# CH340T-BREAKOUT.net
KiCad netlist of a schematic drawn in Altium Designer
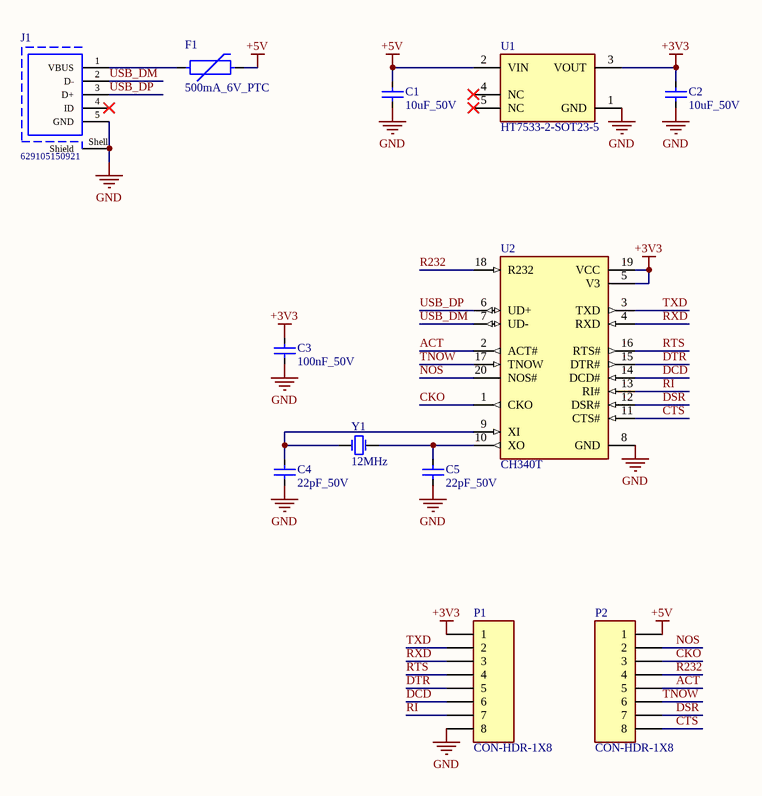
[diagram p0: CH340T-BREAKOUT.SchDoc]

(export (version "E")
  (design (tool "Eeschema 10.0.6"))
  (components
    (comp (ref "C1")
      (value "10uF_50V")
      (footprint "CustomLib-Package:C0805")
      (description "C0805 0.10 μF X7R 30ppm/°C 10.00% 50 V")
      (fields
        (field (name "MANUFACTURER") "KEMET")
        (field (name "MANUFACTURER PART NUMBER") "C0805C104K5RAC7411")
      )
      (libsource (lib "CustomLib-Package") (part "CAPACITOR"))
    )
    (comp (ref "C2")
      (value "10uF_50V")
      (footprint "CustomLib-Package:C0805")
      (description "C0805 0.10 μF X7R 30ppm/°C 10.00% 50 V")
      (fields
        (field (name "MANUFACTURER") "KEMET")
        (field (name "MANUFACTURER PART NUMBER") "C0805C104K5RAC7411")
      )
      (libsource (lib "CustomLib-Package") (part "CAPACITOR"))
    )
    (comp (ref "C3")
      (value "100nF_50V")
      (footprint "CustomLib-Package:C0805")
      (description "C0805 0.10 μF X7R 30ppm/°C 10.00% 50 V")
      (fields
        (field (name "MANUFACTURER") "KEMET")
        (field (name "MANUFACTURER PART NUMBER") "C0805C104K5RAC7411")
      )
      (libsource (lib "CustomLib-Package") (part "CAPACITOR"))
    )
    (comp (ref "C4")
      (value "22pF_50V")
      (footprint "CustomLib-Package:C0805")
      (description "Cap Ceramic 22pF 50V C0G 5% SMD 0603")
      (fields (field (name "Comment") "C0603C220J5GACAUTO"))
      (libsource (lib "CustomLib-Package") (part "CAPACITOR"))
    )
    (comp (ref "C5")
      (value "22pF_50V")
      (footprint "CustomLib-Package:C0805")
      (description "Cap Ceramic 22pF 50V C0G 5% SMD 0603")
      (fields (field (name "Comment") "C0603C220J5GACAUTO"))
      (libsource (lib "CustomLib-Package") (part "CAPACITOR"))
    )
    (comp (ref "F1")
      (value "500mA_6V_PTC")
      (footprint "R0805")
      (description "FUSE 500MA SMD (0805) RESETABLE")
      (fields (field (name "Comment") "MF-PSMF050X-2"))
      (libsource (lib "CustomLib-Package") (part "FUSE-PTC"))
    )
    (comp (ref "J1")
      (value "629105150921")
      (footprint "CON-MICRO-USB-B-SMD-WITH-HOLDER")
      (description "Micro USB 2.0 Type AB Receptacle WR-COM, Horizontal, SMT")
      (fields (field (name "MANUFACTURER") "Wurth Elektronik") (field (name "PUBLISHER") "WurthElektronik"))
      (libsource (lib "CustomLib-Package") (part "CON-MICRO-USB-AB-RCPT-SMD"))
    )
    (comp (ref "P1")
      (value "CON-HDR-1X8")
      (footprint "CON-HDR-1X8-2.54")
      (description "Pin Header, 8-Pin")
      (fields (field (name "PUBLISHER") "Altium Limited"))
      (libsource (lib "CustomLib-Package") (part "CON-HDR-1X8"))
    )
    (comp (ref "P2")
      (value "CON-HDR-1X8")
      (footprint "CON-HDR-1X8-2.54")
      (description "Pin Header, 8-Pin")
      (fields (field (name "PUBLISHER") "Altium Limited"))
      (libsource (lib "") (part "CON-HDR-1X8_1"))
    )
    (comp (ref "U1")
      (value "HT7533-2-SOT23-5")
      (footprint "SOT-23-5")
      (description "100mA 55mV@(1mA) Fixed 3.3V~3.3V Positive 1 30V SOT-23-5 Linear Voltage Regulators (LDO) ROHS")
      (libsource (lib "CustomLib-Package") (part "HT7533-2-SOT23-5"))
    )
    (comp (ref "U2")
      (value "CH340T")
      (footprint "SSOP-20")
      (description "CH340 USB 2.0 to UART Interface Evaluation Board")
      (fields (field (name "MF") "Olimex LTD"))
      (libsource (lib "CustomLib-Package") (part "CH340T"))
    )
    (comp (ref "Y1")
      (value "12MHz")
      (footprint "HC-49-US-TH")
      (description "CRYSTAL 8.0000MHZ 18PF SMD")
      (fields (field (name "TOLERANCE") "20ppm"))
      (libsource (lib "CustomLib-Package") (part "CRYSTAL-2P"))
    )
  )
  (nets
    (net (code "1") (name "+3V3") (class "Default")
      (node (ref "C2") (pin "1") (pinfunction "1_1") (pintype "passive"))
      (node (ref "C3") (pin "1") (pinfunction "1_1") (pintype "passive"))
      (node (ref "P1") (pin "1") (pinfunction "1_1") (pintype "passive"))
      (node (ref "U1") (pin "3") (pinfunction "VOUT_3") (pintype "power_in"))
      (node (ref "U2") (pin "19") (pinfunction "VCC_19") (pintype "power_in"))
      (node (ref "U2") (pin "5") (pinfunction "V3_5") (pintype "power_in"))
    )
    (net (code "2") (name "+5V") (class "Default")
      (node (ref "C1") (pin "1") (pinfunction "1_1") (pintype "passive"))
      (node (ref "F1") (pin "2") (pinfunction "2_2") (pintype "passive"))
      (node (ref "P2") (pin "1") (pinfunction "1_1") (pintype "passive"))
      (node (ref "U1") (pin "2") (pinfunction "VIN_2") (pintype "power_in"))
    )
    (net (code "3") (name "/ACT") (class "Default")
      (node (ref "P2") (pin "5") (pinfunction "5_5") (pintype "passive"))
      (node (ref "U2") (pin "2") (pinfunction "ACT#_2") (pintype "output"))
    )
    (net (code "4") (name "/CKO") (class "Default")
      (node (ref "P2") (pin "3") (pinfunction "3_3") (pintype "passive"))
      (node (ref "U2") (pin "1") (pinfunction "CKO_1") (pintype "output"))
    )
    (net (code "5") (name "/CTS") (class "Default")
      (node (ref "P2") (pin "8") (pinfunction "8_8") (pintype "passive"))
      (node (ref "U2") (pin "11") (pinfunction "CTS#_11") (pintype "input"))
    )
    (net (code "6") (name "/DCD") (class "Default")
      (node (ref "P1") (pin "6") (pinfunction "6_6") (pintype "passive"))
      (node (ref "U2") (pin "14") (pinfunction "DCD#_14") (pintype "input"))
    )
    (net (code "7") (name "/DSR") (class "Default")
      (node (ref "P2") (pin "7") (pinfunction "7_7") (pintype "passive"))
      (node (ref "U2") (pin "12") (pinfunction "DSR#_12") (pintype "input"))
    )
    (net (code "8") (name "/DTR") (class "Default")
      (node (ref "P1") (pin "5") (pinfunction "5_5") (pintype "passive"))
      (node (ref "U2") (pin "15") (pinfunction "DTR#_15") (pintype "output"))
    )
    (net (code "9") (name "/NOS") (class "Default")
      (node (ref "P2") (pin "2") (pinfunction "2_2") (pintype "passive"))
      (node (ref "U2") (pin "20") (pinfunction "NOS#_20") (pintype "power_in"))
    )
    (net (code "10") (name "/R232") (class "Default")
      (node (ref "P2") (pin "4") (pinfunction "4_4") (pintype "passive"))
      (node (ref "U2") (pin "18") (pinfunction "R232_18") (pintype "input"))
    )
    (net (code "11") (name "/RI") (class "Default")
      (node (ref "P1") (pin "7") (pinfunction "7_7") (pintype "passive"))
      (node (ref "U2") (pin "13") (pinfunction "RI#_13") (pintype "input"))
    )
    (net (code "12") (name "/RTS") (class "Default")
      (node (ref "P1") (pin "4") (pinfunction "4_4") (pintype "passive"))
      (node (ref "U2") (pin "16") (pinfunction "RTS#_16") (pintype "output"))
    )
    (net (code "13") (name "/RXD") (class "Default")
      (node (ref "P1") (pin "3") (pinfunction "3_3") (pintype "passive"))
      (node (ref "U2") (pin "4") (pinfunction "RXD_4") (pintype "input"))
    )
    (net (code "14") (name "/TNOW") (class "Default")
      (node (ref "P2") (pin "6") (pinfunction "6_6") (pintype "passive"))
      (node (ref "U2") (pin "17") (pinfunction "TNOW_17") (pintype "input"))
    )
    (net (code "15") (name "/TXD") (class "Default")
      (node (ref "P1") (pin "2") (pinfunction "2_2") (pintype "passive"))
      (node (ref "U2") (pin "3") (pinfunction "TXD_3") (pintype "output"))
    )
    (net (code "16") (name "/USB_DM") (class "Default")
      (node (ref "J1") (pin "2") (pinfunction "D-_2") (pintype "passive"))
      (node (ref "U2") (pin "7") (pinfunction "UD-_7") (pintype "bidirectional"))
    )
    (net (code "17") (name "/USB_DP") (class "Default")
      (node (ref "J1") (pin "3") (pinfunction "D+_3") (pintype "passive"))
      (node (ref "U2") (pin "6") (pinfunction "UD+_6") (pintype "bidirectional"))
    )
    (net (code "18") (name "GND") (class "Default")
      (node (ref "C1") (pin "2") (pinfunction "2_2") (pintype "passive"))
      (node (ref "C2") (pin "2") (pinfunction "2_2") (pintype "passive"))
      (node (ref "C3") (pin "2") (pinfunction "2_2") (pintype "passive"))
      (node (ref "C4") (pin "2") (pinfunction "2_2") (pintype "passive"))
      (node (ref "C5") (pin "2") (pinfunction "2_2") (pintype "passive"))
      (node (ref "J1") (pin "5") (pinfunction "GND_5") (pintype "passive"))
      (node (ref "J1") (pin "Shell") (pinfunction "Shield_Shell") (pintype "passive"))
      (node (ref "P1") (pin "8") (pinfunction "8_8") (pintype "passive"))
      (node (ref "U1") (pin "1") (pinfunction "GND_1") (pintype "power_in"))
      (node (ref "U2") (pin "8") (pinfunction "GND_8") (pintype "power_in"))
    )
    (net (code "19") (name "Net-(J1-VBUS)") (class "Default")
      (node (ref "F1") (pin "1") (pinfunction "1_1") (pintype "passive"))
      (node (ref "J1") (pin "1") (pinfunction "VBUS_1") (pintype "passive"))
    )
    (net (code "20") (name "Net-(U2-XI)") (class "Default")
      (node (ref "C4") (pin "1") (pinfunction "1_1") (pintype "passive"))
      (node (ref "U2") (pin "9") (pinfunction "XI_9") (pintype "input"))
      (node (ref "Y1") (pin "1") (pinfunction "1_1") (pintype "passive"))
    )
    (net (code "21") (name "Net-(U2-XO)") (class "Default")
      (node (ref "C5") (pin "1") (pinfunction "1_1") (pintype "passive"))
      (node (ref "U2") (pin "10") (pinfunction "XO_10") (pintype "output"))
      (node (ref "Y1") (pin "2") (pinfunction "2_2") (pintype "passive"))
    )
    (net (code "22") (name "unconnected-(J1-ID-Pad4)") (class "Default")
      (node (ref "J1") (pin "4") (pinfunction "ID_4") (pintype "passive+no_connect"))
    )
    (net (code "23") (name "unconnected-(U1-NC-Pad4)") (class "Default")
      (node (ref "U1") (pin "4") (pinfunction "NC_4") (pintype "passive+no_connect"))
    )
    (net (code "24") (name "unconnected-(U1-NC-Pad5)") (class "Default")
      (node (ref "U1") (pin "5") (pinfunction "NC_5") (pintype "passive+no_connect"))
    )
  )
)
